# RN41-v14.net
KiCad netlist of a schematic drawn in EAGLE
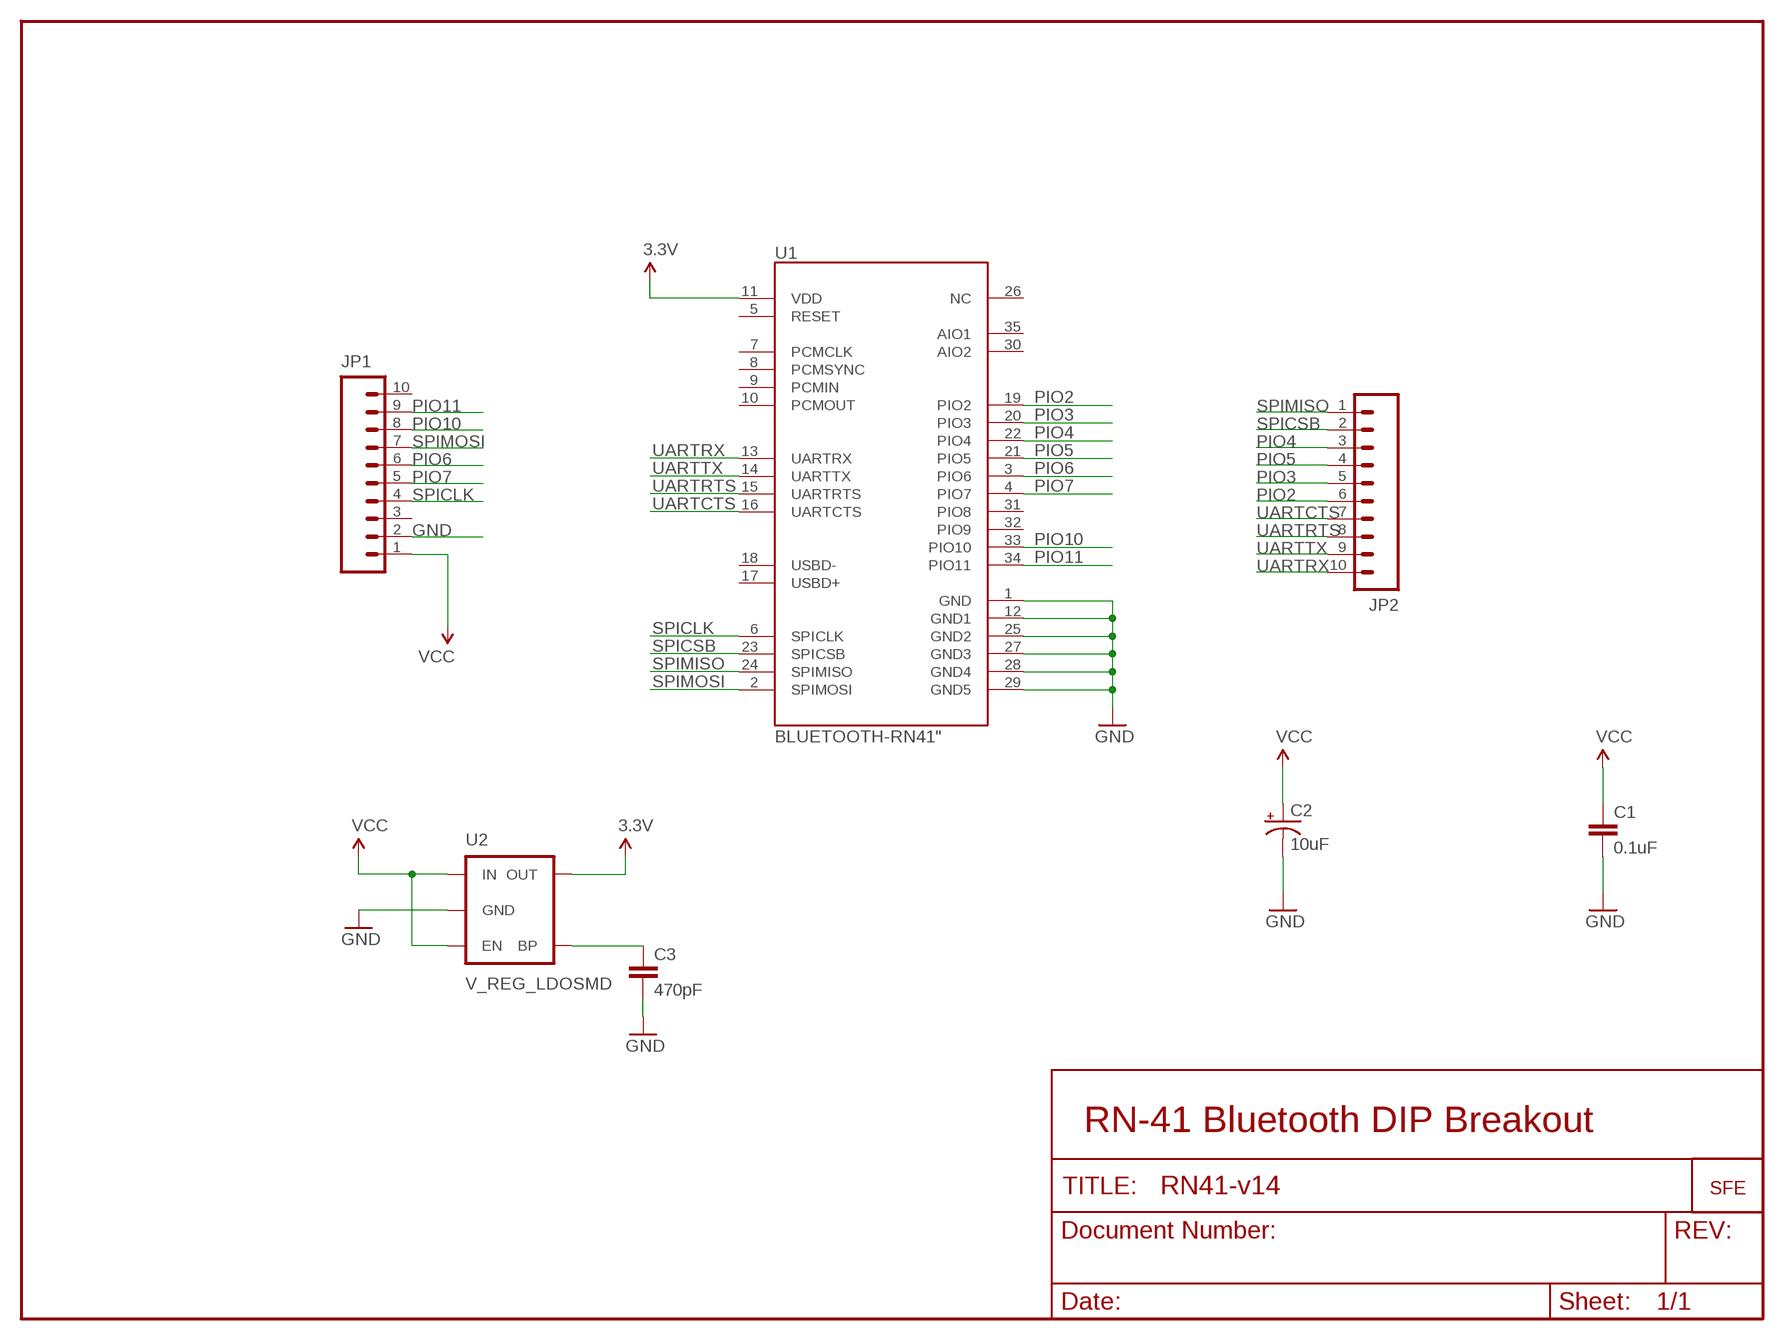
[diagram p0: schematic, sheet 1]

(export (version "E")
  (design (tool "Eeschema 10.0.6"))
  (components
    (comp (ref "C1")
      (value "0.1uF")
      (footprint "eagle-import:0603-CAP")
      (libsource (lib "eagle-import") (part "CAP0603-CAP"))
    )
    (comp (ref "C2")
      (value "10uF")
      (footprint "eagle-import:EIA3216")
      (libsource (lib "eagle-import") (part "CAP_POL1206"))
    )
    (comp (ref "C3")
      (value "470pF")
      (footprint "eagle-import:0603-CAP")
      (libsource (lib "eagle-import") (part "CAP0603-CAP"))
    )
    (comp (ref "JP1")
      (value "M10\"")
      (footprint "eagle-import:1X10")
      (libsource (lib "eagle-import") (part "M10{dblquote}"))
    )
    (comp (ref "JP2")
      (value "M10\"")
      (footprint "eagle-import:1X10")
      (libsource (lib "eagle-import") (part "M10{dblquote}"))
    )
    (comp (ref "U$1")
      (value "LOGO-SFENEW")
      (footprint "eagle-import:SFE-NEW-WEBLOGO")
      (libsource (lib "eagle-import") (part "LOGO-SFENEW"))
    )
    (comp (ref "U1")
      (value "BLUETOOTH-RN41\"")
      (footprint "eagle-import:RN41")
      (libsource (lib "eagle-import") (part "BLUETOOTH-RN41{dblquote}"))
    )
    (comp (ref "U2")
      (value "V_REG_LDOSMD")
      (footprint "eagle-import:SOT23-5")
      (libsource (lib "eagle-import") (part "V_REG_LDOSMD"))
    )
  )
  (nets
    (net (code "1") (name "/PIO2") (class "Default")
      (node (ref "JP2") (pin "6") (pinfunction "6_6") (pintype "passive"))
      (node (ref "U1") (pin "19") (pinfunction "PIO2_19") (pintype "bidirectional"))
    )
    (net (code "2") (name "/PIO3") (class "Default")
      (node (ref "JP2") (pin "5") (pinfunction "5_5") (pintype "passive"))
      (node (ref "U1") (pin "20") (pinfunction "PIO3_20") (pintype "bidirectional"))
    )
    (net (code "3") (name "/PIO4") (class "Default")
      (node (ref "JP2") (pin "3") (pinfunction "3_3") (pintype "passive"))
      (node (ref "U1") (pin "22") (pinfunction "PIO4_22") (pintype "bidirectional"))
    )
    (net (code "4") (name "/PIO5") (class "Default")
      (node (ref "JP2") (pin "4") (pinfunction "4_4") (pintype "passive"))
      (node (ref "U1") (pin "21") (pinfunction "PIO5_21") (pintype "bidirectional"))
    )
    (net (code "5") (name "/PIO6") (class "Default")
      (node (ref "JP1") (pin "6") (pinfunction "6_6") (pintype "passive"))
      (node (ref "U1") (pin "3") (pinfunction "PIO6_3") (pintype "bidirectional"))
    )
    (net (code "6") (name "/PIO7") (class "Default")
      (node (ref "JP1") (pin "5") (pinfunction "5_5") (pintype "passive"))
      (node (ref "U1") (pin "4") (pinfunction "PIO7_4") (pintype "bidirectional"))
    )
    (net (code "7") (name "/PIO10") (class "Default")
      (node (ref "JP1") (pin "8") (pinfunction "8_8") (pintype "passive"))
      (node (ref "U1") (pin "33") (pinfunction "PIO10_33") (pintype "bidirectional"))
    )
    (net (code "8") (name "/PIO11") (class "Default")
      (node (ref "JP1") (pin "9") (pinfunction "9_9") (pintype "passive"))
      (node (ref "U1") (pin "34") (pinfunction "PIO11_34") (pintype "bidirectional"))
    )
    (net (code "9") (name "/SPICLK") (class "Default")
      (node (ref "JP1") (pin "4") (pinfunction "4_4") (pintype "passive"))
      (node (ref "U1") (pin "6") (pinfunction "SPICLK_6") (pintype "bidirectional"))
    )
    (net (code "10") (name "/SPICSB") (class "Default")
      (node (ref "JP2") (pin "2") (pinfunction "2_2") (pintype "passive"))
      (node (ref "U1") (pin "23") (pinfunction "SPICSB_23") (pintype "bidirectional"))
    )
    (net (code "11") (name "/SPIMISO") (class "Default")
      (node (ref "JP2") (pin "1") (pinfunction "1_1") (pintype "passive"))
      (node (ref "U1") (pin "24") (pinfunction "SPIMISO_24") (pintype "bidirectional"))
    )
    (net (code "12") (name "/SPIMOSI") (class "Default")
      (node (ref "JP1") (pin "7") (pinfunction "7_7") (pintype "passive"))
      (node (ref "U1") (pin "2") (pinfunction "SPIMOSI_2") (pintype "bidirectional"))
    )
    (net (code "13") (name "/UARTCTS") (class "Default")
      (node (ref "JP2") (pin "7") (pinfunction "7_7") (pintype "passive"))
      (node (ref "U1") (pin "16") (pinfunction "UARTCTS_16") (pintype "bidirectional"))
    )
    (net (code "14") (name "/UARTRTS") (class "Default")
      (node (ref "JP2") (pin "8") (pinfunction "8_8") (pintype "passive"))
      (node (ref "U1") (pin "15") (pinfunction "UARTRTS_15") (pintype "bidirectional"))
    )
    (net (code "15") (name "/UARTRX") (class "Default")
      (node (ref "JP2") (pin "10") (pinfunction "10_10") (pintype "passive"))
      (node (ref "U1") (pin "13") (pinfunction "UARTRX_13") (pintype "bidirectional"))
    )
    (net (code "16") (name "/UARTTX") (class "Default")
      (node (ref "JP2") (pin "9") (pinfunction "9_9") (pintype "passive"))
      (node (ref "U1") (pin "14") (pinfunction "UARTTX_14") (pintype "bidirectional"))
    )
    (net (code "17") (name "3.3V") (class "Default")
      (node (ref "U1") (pin "11") (pinfunction "VDD_11") (pintype "bidirectional"))
      (node (ref "U2") (pin "5") (pinfunction "OUT_5") (pintype "passive"))
    )
    (net (code "18") (name "GND") (class "Default")
      (node (ref "C1") (pin "2") (pinfunction "2_2") (pintype "passive"))
      (node (ref "C2") (pin "C") (pinfunction "-_C") (pintype "passive"))
      (node (ref "C3") (pin "2") (pinfunction "2_2") (pintype "passive"))
      (node (ref "JP1") (pin "2") (pinfunction "2_2") (pintype "passive"))
      (node (ref "U1") (pin "1") (pinfunction "GND_1") (pintype "bidirectional"))
      (node (ref "U1") (pin "12") (pinfunction "GND1_12") (pintype "bidirectional"))
      (node (ref "U1") (pin "25") (pinfunction "GND2_25") (pintype "bidirectional"))
      (node (ref "U1") (pin "27") (pinfunction "GND3_27") (pintype "bidirectional"))
      (node (ref "U1") (pin "28") (pinfunction "GND4_28") (pintype "bidirectional"))
      (node (ref "U1") (pin "29") (pinfunction "GND5_29") (pintype "bidirectional"))
      (node (ref "U2") (pin "2") (pinfunction "GND_2") (pintype "input"))
    )
    (net (code "19") (name "Net-(U2-BP)") (class "Default")
      (node (ref "C3") (pin "1") (pinfunction "1_1") (pintype "passive"))
      (node (ref "U2") (pin "4") (pinfunction "BP_4") (pintype "input"))
    )
    (net (code "20") (name "VCC") (class "Default")
      (node (ref "C1") (pin "1") (pinfunction "1_1") (pintype "passive"))
      (node (ref "C2") (pin "A") (pinfunction "+_A") (pintype "passive"))
      (node (ref "JP1") (pin "1") (pinfunction "1_1") (pintype "passive"))
      (node (ref "U2") (pin "1") (pinfunction "IN_1") (pintype "input"))
      (node (ref "U2") (pin "3") (pinfunction "EN_3") (pintype "input"))
    )
    (net (code "21") (name "unconnected-(JP1-Pad3)") (class "Default")
      (node (ref "JP1") (pin "3") (pinfunction "3_3") (pintype "passive"))
    )
    (net (code "22") (name "unconnected-(JP1-Pad10)") (class "Default")
      (node (ref "JP1") (pin "10") (pinfunction "10_10") (pintype "passive"))
    )
    (net (code "23") (name "unconnected-(U1-AIO1-Pad35)") (class "Default")
      (node (ref "U1") (pin "35") (pinfunction "AIO1_35") (pintype "bidirectional"))
    )
    (net (code "24") (name "unconnected-(U1-AIO2-Pad30)") (class "Default")
      (node (ref "U1") (pin "30") (pinfunction "AIO2_30") (pintype "bidirectional"))
    )
    (net (code "25") (name "unconnected-(U1-NC-Pad26)") (class "Default")
      (node (ref "U1") (pin "26") (pinfunction "NC_26") (pintype "bidirectional"))
    )
    (net (code "26") (name "unconnected-(U1-PCMCLK-Pad7)") (class "Default")
      (node (ref "U1") (pin "7") (pinfunction "PCMCLK_7") (pintype "bidirectional"))
    )
    (net (code "27") (name "unconnected-(U1-PCMIN-Pad9)") (class "Default")
      (node (ref "U1") (pin "9") (pinfunction "PCMIN_9") (pintype "bidirectional"))
    )
    (net (code "28") (name "unconnected-(U1-PCMOUT-Pad10)") (class "Default")
      (node (ref "U1") (pin "10") (pinfunction "PCMOUT_10") (pintype "bidirectional"))
    )
    (net (code "29") (name "unconnected-(U1-PCMSYNC-Pad8)") (class "Default")
      (node (ref "U1") (pin "8") (pinfunction "PCMSYNC_8") (pintype "bidirectional"))
    )
    (net (code "30") (name "unconnected-(U1-PIO8-Pad31)") (class "Default")
      (node (ref "U1") (pin "31") (pinfunction "PIO8_31") (pintype "bidirectional"))
    )
    (net (code "31") (name "unconnected-(U1-PIO9-Pad32)") (class "Default")
      (node (ref "U1") (pin "32") (pinfunction "PIO9_32") (pintype "bidirectional"))
    )
    (net (code "32") (name "unconnected-(U1-RESET-Pad5)") (class "Default")
      (node (ref "U1") (pin "5") (pinfunction "RESET_5") (pintype "bidirectional"))
    )
    (net (code "33") (name "unconnected-(U1-USBD+-Pad17)") (class "Default")
      (node (ref "U1") (pin "17") (pinfunction "USBD+_17") (pintype "bidirectional"))
    )
    (net (code "34") (name "unconnected-(U1-USBD--Pad18)") (class "Default")
      (node (ref "U1") (pin "18") (pinfunction "USBD-_18") (pintype "bidirectional"))
    )
  )
)
